# Master_node.net
KiCad netlist of a schematic drawn in EAGLE
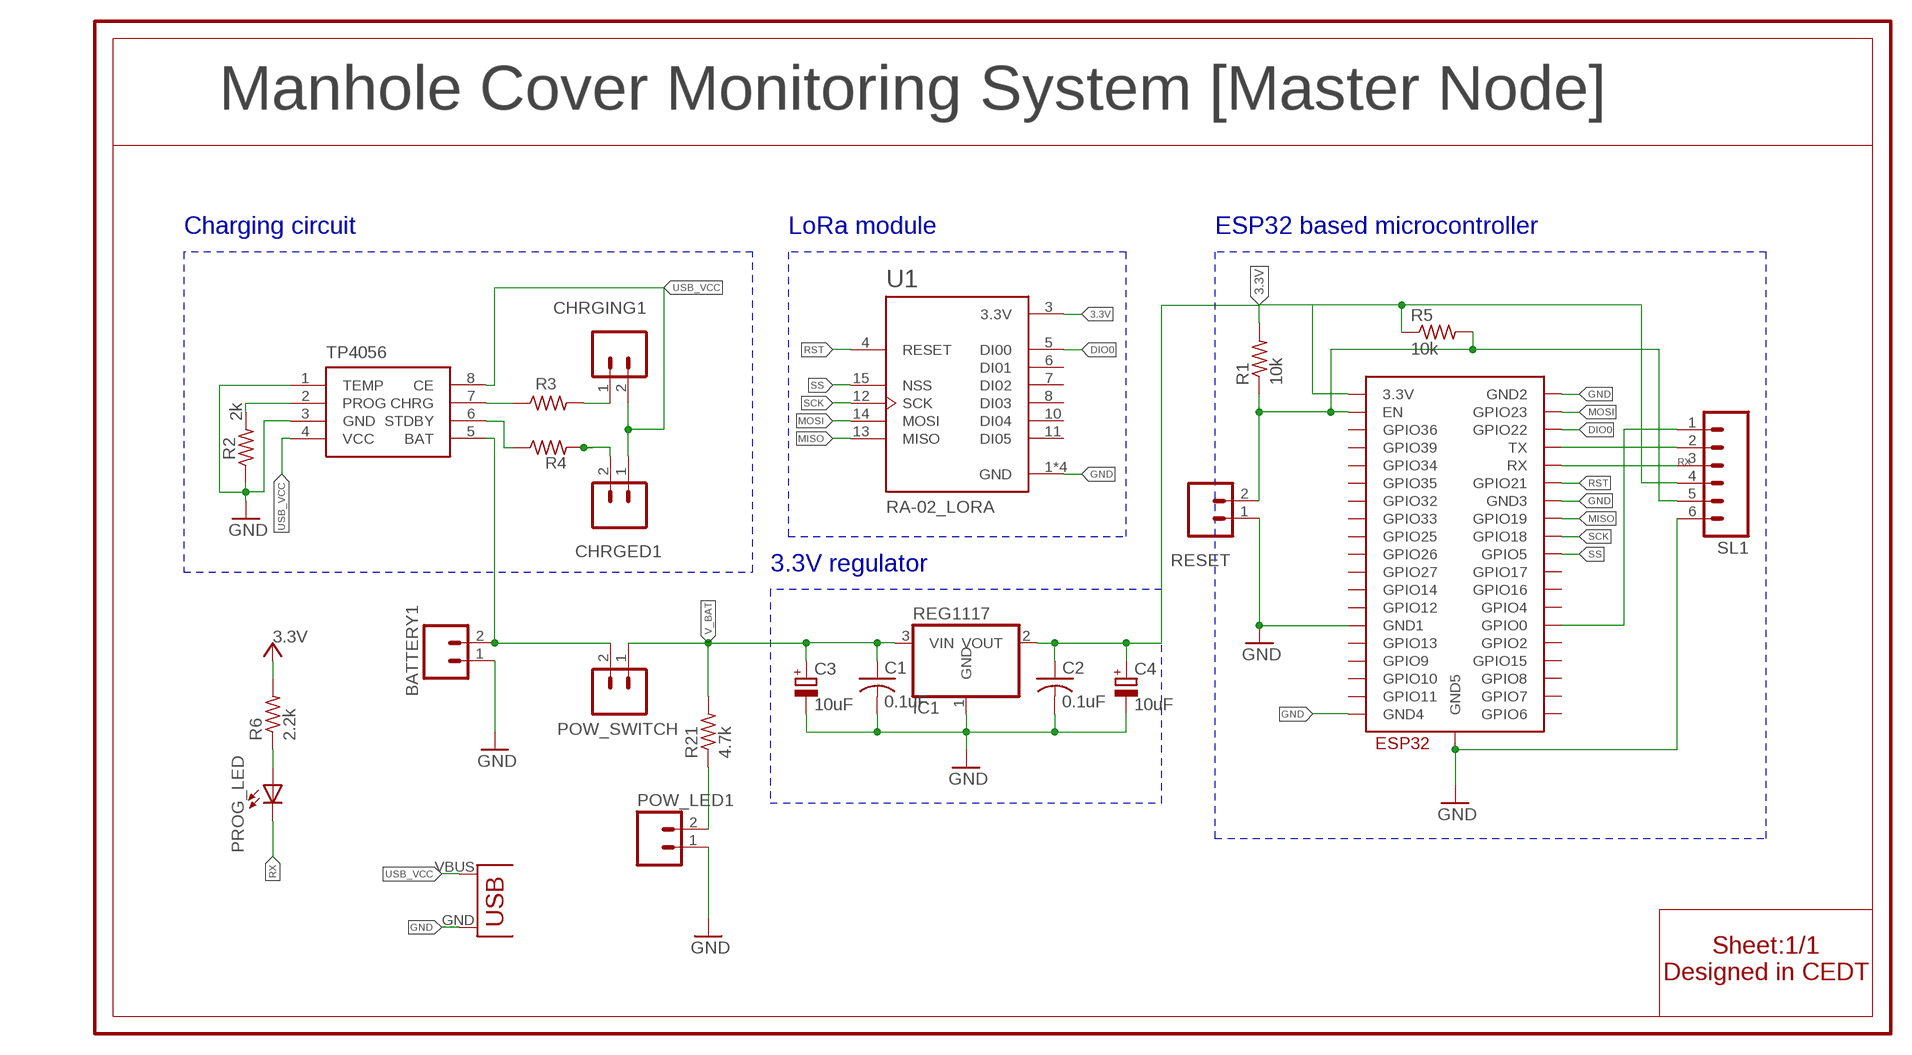
[diagram p0: schematic, sheet 1]

(export (version "E")
  (design (tool "Eeschema 10.0.6"))
  (components
    (comp (ref "BATTERY1")
      (value "M02")
      (footprint "eagle-import:02P")
      (libsource (lib "eagle-import") (part "M02"))
    )
    (comp (ref "C1")
      (value "0.1uF")
      (footprint "eagle-import:C0805")
      (libsource (lib "eagle-import") (part "CAP0805"))
    )
    (comp (ref "C2")
      (value "0.1uF")
      (footprint "eagle-import:C0805")
      (libsource (lib "eagle-import") (part "CAP0805"))
    )
    (comp (ref "C3")
      (value "10uF")
      (footprint "eagle-import:CAPMP3528X210N")
      (libsource (lib "eagle-import") (part "C-POLTANTALUM-1411(3528-METRIC)_"))
    )
    (comp (ref "C4")
      (value "10uF")
      (footprint "eagle-import:CAPMP3528X210N")
      (libsource (lib "eagle-import") (part "C-POLTANTALUM-1411(3528-METRIC)_"))
    )
    (comp (ref "CHRGED1")
      (value "M02")
      (footprint "eagle-import:02P")
      (libsource (lib "eagle-import") (part "M02"))
    )
    (comp (ref "CHRGING1")
      (value "M02")
      (footprint "eagle-import:02P")
      (libsource (lib "eagle-import") (part "M02"))
    )
    (comp (ref "IC1")
      (value "REG1117")
      (footprint "eagle-import:SOT223")
      (libsource (lib "eagle-import") (part "REG1117"))
    )
    (comp (ref "POW_LED1")
      (value "M02")
      (footprint "eagle-import:02P")
      (libsource (lib "eagle-import") (part "M02"))
    )
    (comp (ref "POW_SWITCH")
      (value "M02")
      (footprint "eagle-import:02P")
      (libsource (lib "eagle-import") (part "M02"))
    )
    (comp (ref "PROG_LED")
      (value "LED0603")
      (footprint "eagle-import:CHIPLED_0603")
      (libsource (lib "eagle-import") (part "LED0603"))
    )
    (comp (ref "R1")
      (value "10k")
      (footprint "eagle-import:0207_7")
      (libsource (lib "eagle-import") (part "CEDT_JANUARY_2015_v6_RESISTOR0207/7"))
    )
    (comp (ref "R2")
      (value "2k")
      (footprint "eagle-import:0207_7")
      (libsource (lib "eagle-import") (part "RESISTOR0207/7"))
    )
    (comp (ref "R3")
      (value "470")
      (footprint "eagle-import:0207_7")
      (libsource (lib "eagle-import") (part "RESISTOR0207/7"))
    )
    (comp (ref "R4")
      (value "470")
      (footprint "eagle-import:0207_7")
      (libsource (lib "eagle-import") (part "RESISTOR0207/7"))
    )
    (comp (ref "R5")
      (value "10k")
      (footprint "eagle-import:R0805")
      (libsource (lib "eagle-import") (part "CEDT_JANUARY_2015_v6_RESISTOR0805"))
    )
    (comp (ref "R6")
      (value "2.2k")
      (footprint "eagle-import:R0805")
      (libsource (lib "eagle-import") (part "CEDT_JANUARY_2015_v6_RESISTOR0805"))
    )
    (comp (ref "R21")
      (value "4.7k")
      (footprint "eagle-import:0207_10")
      (libsource (lib "eagle-import") (part "R-US_0207/10"))
    )
    (comp (ref "RESET")
      (value "M02")
      (footprint "eagle-import:02P")
      (libsource (lib "eagle-import") (part "M02"))
    )
    (comp (ref "SL1")
      (value "M06")
      (footprint "eagle-import:06P")
      (libsource (lib "eagle-import") (part "M06"))
    )
    (comp (ref "TP4056")
      (value "TP4056")
      (footprint "eagle-import:SOP-8")
      (libsource (lib "eagle-import") (part "TP4056"))
    )
    (comp (ref "U$1")
      (value "ESP32-WROOM")
      (footprint "eagle-import:ESP32-WROOM")
      (libsource (lib "eagle-import") (part "ESP32-WROOM"))
    )
    (comp (ref "U$3")
      (value "USB(POWER)")
      (footprint "eagle-import:USB(POWER)")
      (libsource (lib "eagle-import") (part "USB(POWER)"))
    )
    (comp (ref "U1")
      (value "RA-02_LORA")
      (footprint "eagle-import:MODULE_RA-02_LORA")
      (fields (field (name "MF") "AI-Thinker") (field (name "MP") "Ra-02 LoRa"))
      (libsource (lib "eagle-import") (part "RA-02_LORA"))
    )
  )
  (nets
    (net (code "1") (name "3.3V") (class "Default")
      (node (ref "C2") (pin "1") (pinfunction "1_1") (pintype "passive"))
      (node (ref "C4") (pin "1") (pinfunction "+_1") (pintype "passive"))
      (node (ref "IC1") (pin "2") (pinfunction "VOUT_2") (pintype "output"))
      (node (ref "R1") (pin "2") (pinfunction "2_2") (pintype "passive"))
      (node (ref "R5") (pin "1") (pinfunction "1_1") (pintype "passive"))
      (node (ref "R6") (pin "2") (pinfunction "2_2") (pintype "passive"))
      (node (ref "SL1") (pin "4") (pinfunction "4_4") (pintype "passive"))
      (node (ref "U$1") (pin "3V3") (pinfunction "3.3V_3V3") (pintype "bidirectional"))
      (node (ref "U1") (pin "3") (pinfunction "3.3V_3") (pintype "power_in"))
    )
    (net (code "2") (name "DIO0") (class "Default")
      (node (ref "U$1") (pin "IO22") (pinfunction "GPIO22_IO22") (pintype "bidirectional"))
      (node (ref "U1") (pin "5") (pinfunction "DI00_5") (pintype "bidirectional"))
    )
    (net (code "3") (name "GND") (class "Default")
      (node (ref "BATTERY1") (pin "1") (pinfunction "1_1") (pintype "passive"))
      (node (ref "C1") (pin "2") (pinfunction "2_2") (pintype "passive"))
      (node (ref "C2") (pin "2") (pinfunction "2_2") (pintype "passive"))
      (node (ref "C3") (pin "2") (pinfunction "-_2") (pintype "passive"))
      (node (ref "C4") (pin "2") (pinfunction "-_2") (pintype "passive"))
      (node (ref "IC1") (pin "1") (pinfunction "GND_1") (pintype "power_in"))
      (node (ref "POW_LED1") (pin "1") (pinfunction "1_1") (pintype "passive"))
      (node (ref "R2") (pin "1") (pinfunction "1_1") (pintype "passive"))
      (node (ref "RESET") (pin "1") (pinfunction "1_1") (pintype "passive"))
      (node (ref "SL1") (pin "6") (pinfunction "6_6") (pintype "passive"))
      (node (ref "TP4056") (pin "1") (pinfunction "TEMP_1") (pintype "bidirectional"))
      (node (ref "TP4056") (pin "3") (pinfunction "GND_3") (pintype "bidirectional"))
      (node (ref "U$1") (pin "GND1") (pinfunction "GND1_GND1") (pintype "bidirectional"))
      (node (ref "U$1") (pin "GND2") (pinfunction "GND2_GND2") (pintype "bidirectional"))
      (node (ref "U$1") (pin "GND3") (pinfunction "GND3_GND3") (pintype "bidirectional"))
      (node (ref "U$1") (pin "GND4") (pinfunction "GND4_GND4") (pintype "bidirectional"))
      (node (ref "U$1") (pin "GND5") (pinfunction "GND5_GND5") (pintype "bidirectional"))
      (node (ref "U$3") (pin "GND") (pinfunction "GND_GND") (pintype "power_in"))
      (node (ref "U1") (pin "1") (pinfunction "GND_1") (pintype "power_in"))
      (node (ref "U1") (pin "16") (pinfunction "GND_16") (pintype "power_in"))
      (node (ref "U1") (pin "2") (pinfunction "GND_2") (pintype "power_in"))
      (node (ref "U1") (pin "9") (pinfunction "GND_9") (pintype "power_in"))
    )
    (net (code "4") (name "MISO") (class "Default")
      (node (ref "U$1") (pin "IO19") (pinfunction "GPIO19_IO19") (pintype "bidirectional"))
      (node (ref "U1") (pin "13") (pinfunction "MISO_13") (pintype "output"))
    )
    (net (code "5") (name "MOSI") (class "Default")
      (node (ref "U$1") (pin "IO23") (pinfunction "GPIO23_IO23") (pintype "bidirectional"))
      (node (ref "U1") (pin "14") (pinfunction "MOSI_14") (pintype "input"))
    )
    (net (code "6") (name "Net-(CHRGED1-Pad2)") (class "Default")
      (node (ref "CHRGED1") (pin "2") (pinfunction "2_2") (pintype "passive"))
      (node (ref "R4") (pin "2") (pinfunction "2_2") (pintype "passive"))
    )
    (net (code "7") (name "Net-(CHRGING1-Pad1)") (class "Default")
      (node (ref "CHRGING1") (pin "1") (pinfunction "1_1") (pintype "passive"))
      (node (ref "R3") (pin "2") (pinfunction "2_2") (pintype "passive"))
    )
    (net (code "8") (name "Net-(POW_LED1-Pad2)") (class "Default")
      (node (ref "POW_LED1") (pin "2") (pinfunction "2_2") (pintype "passive"))
      (node (ref "R21") (pin "1") (pinfunction "1_1") (pintype "passive"))
    )
    (net (code "9") (name "Net-(PROG_LED-PadA)") (class "Default")
      (node (ref "PROG_LED") (pin "A") (pinfunction "A_A") (pintype "passive"))
      (node (ref "R6") (pin "1") (pinfunction "1_1") (pintype "passive"))
    )
    (net (code "10") (name "Net-(R1-Pad1)") (class "Default")
      (node (ref "R1") (pin "1") (pinfunction "1_1") (pintype "passive"))
      (node (ref "R5") (pin "2") (pinfunction "2_2") (pintype "passive"))
      (node (ref "RESET") (pin "2") (pinfunction "2_2") (pintype "passive"))
      (node (ref "SL1") (pin "5") (pinfunction "5_5") (pintype "passive"))
      (node (ref "U$1") (pin "EN") (pinfunction "EN_EN") (pintype "bidirectional"))
    )
    (net (code "11") (name "Net-(SL1-Pad2)") (class "Default")
      (node (ref "SL1") (pin "2") (pinfunction "2_2") (pintype "passive"))
      (node (ref "U$1") (pin "TX") (pinfunction "TX_TX") (pintype "bidirectional"))
    )
    (net (code "12") (name "Net-(TP4056-BAT)") (class "Default")
      (node (ref "BATTERY1") (pin "2") (pinfunction "2_2") (pintype "passive"))
      (node (ref "POW_SWITCH") (pin "2") (pinfunction "2_2") (pintype "passive"))
      (node (ref "TP4056") (pin "5") (pinfunction "BAT_5") (pintype "bidirectional"))
    )
    (net (code "13") (name "Net-(TP4056-CHRG)") (class "Default")
      (node (ref "R3") (pin "1") (pinfunction "1_1") (pintype "passive"))
      (node (ref "TP4056") (pin "7") (pinfunction "CHRG_7") (pintype "bidirectional"))
    )
    (net (code "14") (name "Net-(TP4056-PROG)") (class "Default")
      (node (ref "R2") (pin "2") (pinfunction "2_2") (pintype "passive"))
      (node (ref "TP4056") (pin "2") (pinfunction "PROG_2") (pintype "bidirectional"))
    )
    (net (code "15") (name "Net-(TP4056-STDBY)") (class "Default")
      (node (ref "R4") (pin "1") (pinfunction "1_1") (pintype "passive"))
      (node (ref "TP4056") (pin "6") (pinfunction "STDBY_6") (pintype "bidirectional"))
    )
    (net (code "16") (name "Net-(U$1-GPIO0)") (class "Default")
      (node (ref "SL1") (pin "1") (pinfunction "1_1") (pintype "passive"))
      (node (ref "U$1") (pin "IO0") (pinfunction "GPIO0_IO0") (pintype "bidirectional"))
    )
    (net (code "17") (name "RST") (class "Default")
      (node (ref "U$1") (pin "IO21") (pinfunction "GPIO21_IO21") (pintype "bidirectional"))
      (node (ref "U1") (pin "4") (pinfunction "RESET_4") (pintype "input"))
    )
    (net (code "18") (name "RX") (class "Default")
      (node (ref "PROG_LED") (pin "C") (pinfunction "C_C") (pintype "passive"))
      (node (ref "SL1") (pin "3") (pinfunction "3_3") (pintype "passive"))
      (node (ref "U$1") (pin "RX") (pinfunction "RX_RX") (pintype "bidirectional"))
    )
    (net (code "19") (name "SCK") (class "Default")
      (node (ref "U$1") (pin "IO18") (pinfunction "GPIO18_IO18") (pintype "bidirectional"))
      (node (ref "U1") (pin "12") (pinfunction "SCK_12") (pintype "input"))
    )
    (net (code "20") (name "SS") (class "Default")
      (node (ref "U$1") (pin "IO5") (pinfunction "GPIO5_IO5") (pintype "bidirectional"))
      (node (ref "U1") (pin "15") (pinfunction "NSS_15") (pintype "input"))
    )
    (net (code "21") (name "USB_VCC") (class "Default")
      (node (ref "CHRGED1") (pin "1") (pinfunction "1_1") (pintype "passive"))
      (node (ref "CHRGING1") (pin "2") (pinfunction "2_2") (pintype "passive"))
      (node (ref "TP4056") (pin "4") (pinfunction "VCC_4") (pintype "bidirectional"))
      (node (ref "TP4056") (pin "8") (pinfunction "CE_8") (pintype "bidirectional"))
      (node (ref "U$3") (pin "VBUS") (pinfunction "VCC_VBUS") (pintype "power_in"))
    )
    (net (code "22") (name "V_BAT") (class "Default")
      (node (ref "C1") (pin "1") (pinfunction "1_1") (pintype "passive"))
      (node (ref "C3") (pin "1") (pinfunction "+_1") (pintype "passive"))
      (node (ref "IC1") (pin "3") (pinfunction "VIN_3") (pintype "input"))
      (node (ref "POW_SWITCH") (pin "1") (pinfunction "1_1") (pintype "passive"))
      (node (ref "R21") (pin "2") (pinfunction "2_2") (pintype "passive"))
    )
    (net (code "23") (name "unconnected-(U$1-GPIO2-PadIO2)") (class "Default")
      (node (ref "U$1") (pin "IO2") (pinfunction "GPIO2_IO2") (pintype "bidirectional"))
    )
    (net (code "24") (name "unconnected-(U$1-GPIO4-PadIO4)") (class "Default")
      (node (ref "U$1") (pin "IO4") (pinfunction "GPIO4_IO4") (pintype "bidirectional"))
    )
    (net (code "25") (name "unconnected-(U$1-GPIO6-PadCLK)") (class "Default")
      (node (ref "U$1") (pin "CLK") (pinfunction "GPIO6_CLK") (pintype "bidirectional"))
    )
    (net (code "26") (name "unconnected-(U$1-GPIO7-PadSD0)") (class "Default")
      (node (ref "U$1") (pin "SD0") (pinfunction "GPIO7_SD0") (pintype "bidirectional"))
    )
    (net (code "27") (name "unconnected-(U$1-GPIO8-PadSD1)") (class "Default")
      (node (ref "U$1") (pin "SD1") (pinfunction "GPIO8_SD1") (pintype "bidirectional"))
    )
    (net (code "28") (name "unconnected-(U$1-GPIO9-PadSD2)") (class "Default")
      (node (ref "U$1") (pin "SD2") (pinfunction "GPIO9_SD2") (pintype "bidirectional"))
    )
    (net (code "29") (name "unconnected-(U$1-GPIO10-PadSD3)") (class "Default")
      (node (ref "U$1") (pin "SD3") (pinfunction "GPIO10_SD3") (pintype "bidirectional"))
    )
    (net (code "30") (name "unconnected-(U$1-GPIO11-PadCMD)") (class "Default")
      (node (ref "U$1") (pin "CMD") (pinfunction "GPIO11_CMD") (pintype "bidirectional"))
    )
    (net (code "31") (name "unconnected-(U$1-GPIO12-PadIO12)") (class "Default")
      (node (ref "U$1") (pin "IO12") (pinfunction "GPIO12_IO12") (pintype "bidirectional"))
    )
    (net (code "32") (name "unconnected-(U$1-GPIO13-PadIO13)") (class "Default")
      (node (ref "U$1") (pin "IO13") (pinfunction "GPIO13_IO13") (pintype "bidirectional"))
    )
    (net (code "33") (name "unconnected-(U$1-GPIO14-PadIO14)") (class "Default")
      (node (ref "U$1") (pin "IO14") (pinfunction "GPIO14_IO14") (pintype "bidirectional"))
    )
    (net (code "34") (name "unconnected-(U$1-GPIO15-PadIO15)") (class "Default")
      (node (ref "U$1") (pin "IO15") (pinfunction "GPIO15_IO15") (pintype "bidirectional"))
    )
    (net (code "35") (name "unconnected-(U$1-GPIO16-PadIO16)") (class "Default")
      (node (ref "U$1") (pin "IO16") (pinfunction "GPIO16_IO16") (pintype "bidirectional"))
    )
    (net (code "36") (name "unconnected-(U$1-GPIO17-PadIO17)") (class "Default")
      (node (ref "U$1") (pin "IO17") (pinfunction "GPIO17_IO17") (pintype "bidirectional"))
    )
    (net (code "37") (name "unconnected-(U$1-GPIO25-PadIO25)") (class "Default")
      (node (ref "U$1") (pin "IO25") (pinfunction "GPIO25_IO25") (pintype "bidirectional"))
    )
    (net (code "38") (name "unconnected-(U$1-GPIO26-PadIO26)") (class "Default")
      (node (ref "U$1") (pin "IO26") (pinfunction "GPIO26_IO26") (pintype "bidirectional"))
    )
    (net (code "39") (name "unconnected-(U$1-GPIO27-PadIO27)") (class "Default")
      (node (ref "U$1") (pin "IO27") (pinfunction "GPIO27_IO27") (pintype "bidirectional"))
    )
    (net (code "40") (name "unconnected-(U$1-GPIO32-PadIO32)") (class "Default")
      (node (ref "U$1") (pin "IO32") (pinfunction "GPIO32_IO32") (pintype "bidirectional"))
    )
    (net (code "41") (name "unconnected-(U$1-GPIO33-PadIO33)") (class "Default")
      (node (ref "U$1") (pin "IO33") (pinfunction "GPIO33_IO33") (pintype "bidirectional"))
    )
    (net (code "42") (name "unconnected-(U$1-GPIO34-PadIO34)") (class "Default")
      (node (ref "U$1") (pin "IO34") (pinfunction "GPIO34_IO34") (pintype "bidirectional"))
    )
    (net (code "43") (name "unconnected-(U$1-GPIO35-PadIO35)") (class "Default")
      (node (ref "U$1") (pin "IO35") (pinfunction "GPIO35_IO35") (pintype "bidirectional"))
    )
    (net (code "44") (name "unconnected-(U$1-GPIO36-PadSENSOR_VP)") (class "Default")
      (node (ref "U$1") (pin "SENSOR_VP") (pinfunction "GPIO36_SENSOR_VP") (pintype "bidirectional"))
    )
    (net (code "45") (name "unconnected-(U$1-GPIO39-PadSENSOR_VN)") (class "Default")
      (node (ref "U$1") (pin "SENSOR_VN") (pinfunction "GPIO39_SENSOR_VN") (pintype "bidirectional"))
    )
    (net (code "46") (name "unconnected-(U1-DI01-Pad6)") (class "Default")
      (node (ref "U1") (pin "6") (pinfunction "DI01_6") (pintype "bidirectional"))
    )
    (net (code "47") (name "unconnected-(U1-DI02-Pad7)") (class "Default")
      (node (ref "U1") (pin "7") (pinfunction "DI02_7") (pintype "bidirectional"))
    )
    (net (code "48") (name "unconnected-(U1-DI03-Pad8)") (class "Default")
      (node (ref "U1") (pin "8") (pinfunction "DI03_8") (pintype "bidirectional"))
    )
    (net (code "49") (name "unconnected-(U1-DI04-Pad10)") (class "Default")
      (node (ref "U1") (pin "10") (pinfunction "DI04_10") (pintype "bidirectional"))
    )
    (net (code "50") (name "unconnected-(U1-DI05-Pad11)") (class "Default")
      (node (ref "U1") (pin "11") (pinfunction "DI05_11") (pintype "bidirectional"))
    )
  )
)
